# random-keypad-interface-board-v01.net
KiCad netlist of a schematic drawn in EAGLE
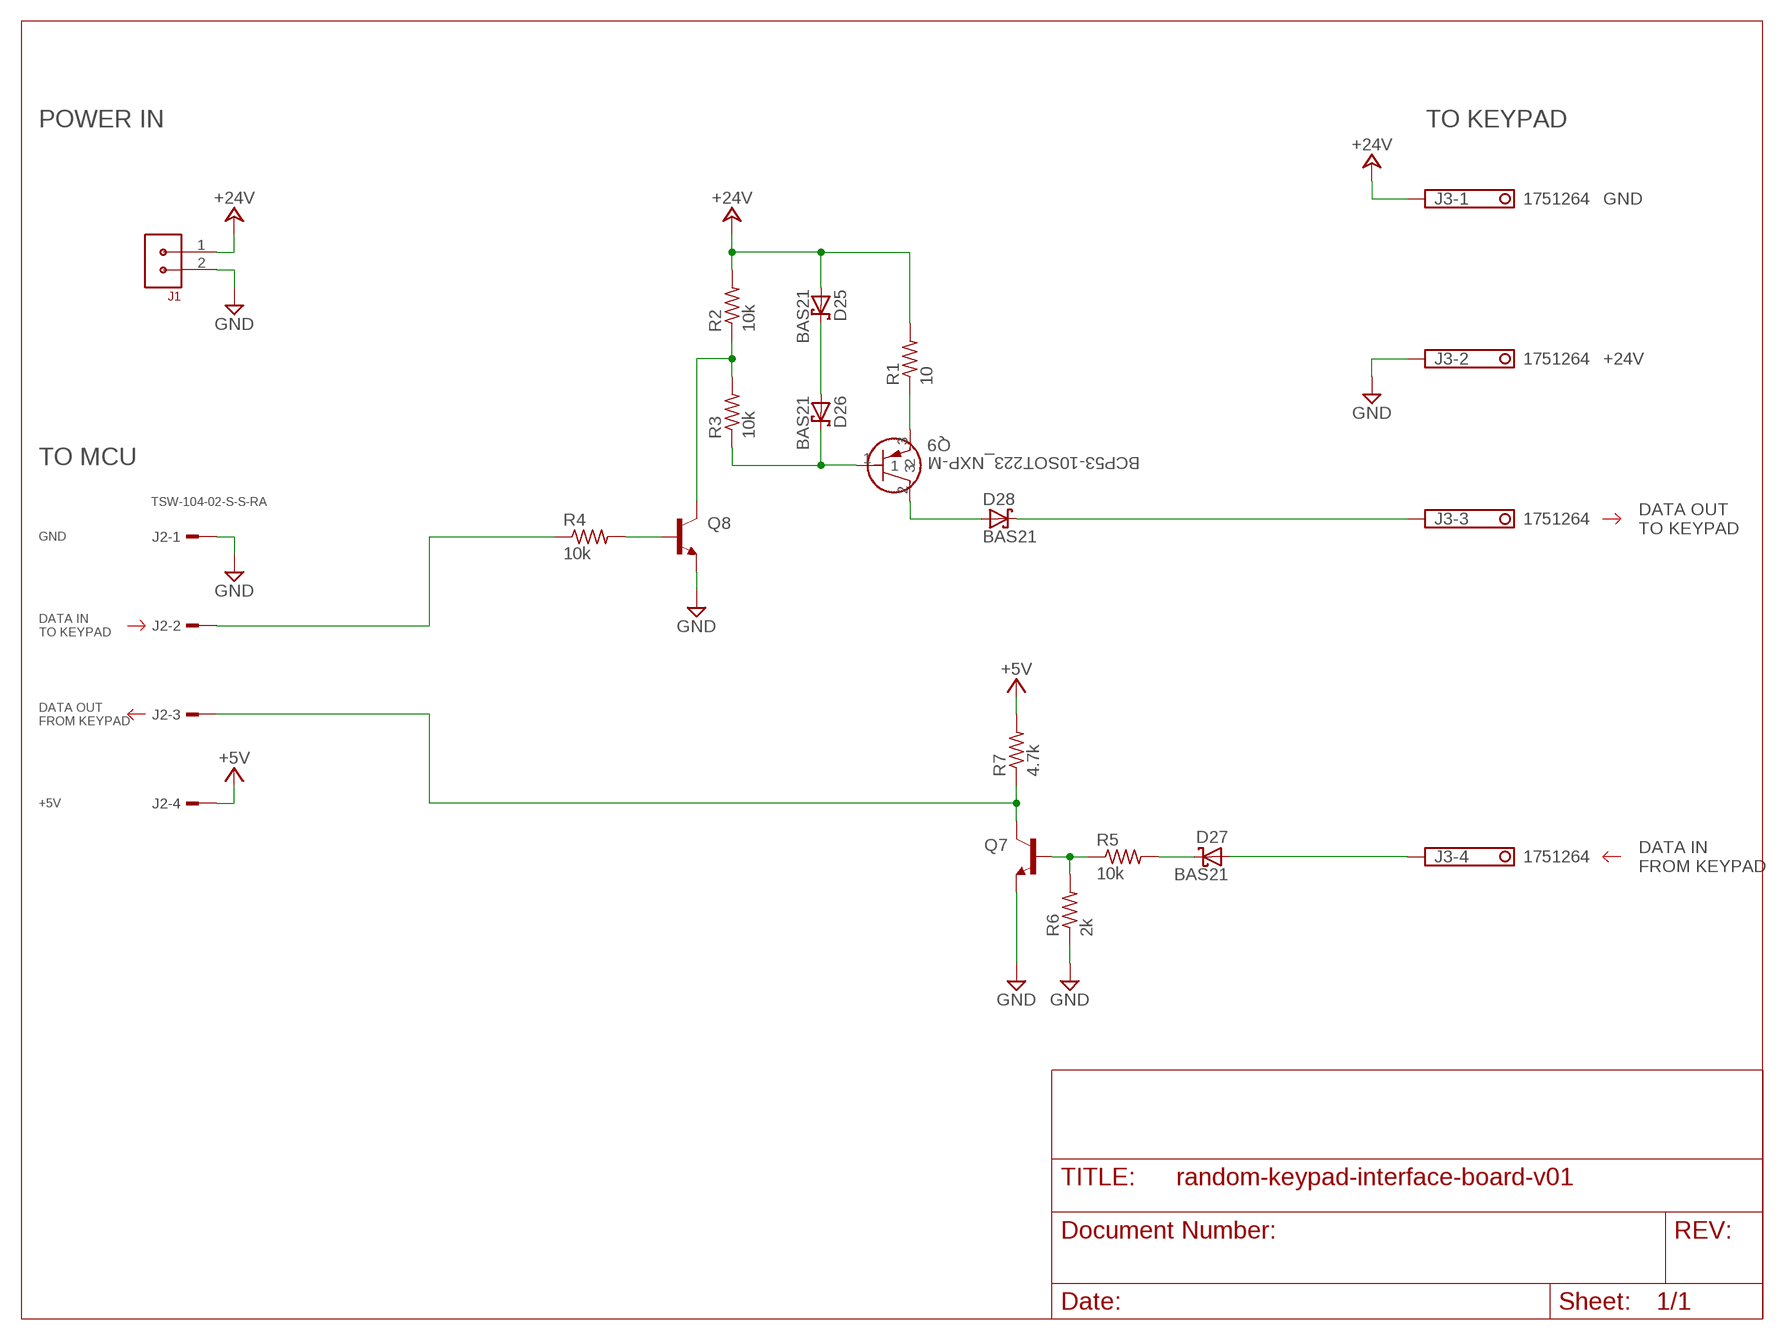
[diagram p0: schematic, sheet 1]

(export (version "E")
  (design (tool "Eeschema 10.0.6"))
  (components
    (comp (ref "D25")
      (value "BAS21")
      (footprint "eagle-import:SOT23")
      (libsource (lib "eagle-import") (part "BAS40"))
    )
    (comp (ref "D26")
      (value "BAS21")
      (footprint "eagle-import:SOT23")
      (libsource (lib "eagle-import") (part "BAS40"))
    )
    (comp (ref "D27")
      (value "BAS21")
      (footprint "eagle-import:SOT23")
      (libsource (lib "eagle-import") (part "BAS40"))
    )
    (comp (ref "D28")
      (value "BAS21")
      (footprint "eagle-import:SOT23")
      (libsource (lib "eagle-import") (part "BAS40"))
    )
    (comp (ref "J1")
      (value "CON-3.81MM-1X2-PHOENIX")
      (footprint "eagle-import:CON-PHOENIX-3.81-1X2-RA")
      (libsource (lib "eagle-import") (part "CON-3.81MM-1X2-PHOENIX"))
    )
    (comp (ref "J2")
      (value "TSW-104-02-S-S-RA")
      (footprint "eagle-import:TSW-104-02-S-S-RA")
      (libsource (lib "eagle-import") (part "TSW-104-02-S-S-RA"))
    )
    (comp (ref "J3")
      (value "1751264")
      (footprint "eagle-import:1751264")
      (libsource (lib "eagle-import") (part "1751264"))
    )
    (comp (ref "Q7")
      (value "BC817-40-NPN-SOT23-BEC")
      (footprint "eagle-import:SOT23-BEC")
      (libsource (lib "eagle-import") (part "-NPN-SOT23-BECBC817-40"))
    )
    (comp (ref "Q8")
      (value "BC817-40-NPN-SOT23-BEC")
      (footprint "eagle-import:SOT23-BEC")
      (libsource (lib "eagle-import") (part "-NPN-SOT23-BECBC817-40"))
    )
    (comp (ref "Q9")
      (value "BCP53-10SOT223_NXP-M")
      (footprint "eagle-import:SOT223_NXP-M")
      (fields
        (field (name "MANUFACTURER_PART_NUMBER") "BCP53-10")
        (field (name "COPYRIGHT") "Copyright (C) 2021 Ultra Librarian. All rights reserved.")
      )
      (libsource (lib "eagle-import") (part "BCP53-10SOT223_NXP-M"))
    )
    (comp (ref "R1")
      (value "10")
      (footprint "eagle-import:R0603")
      (libsource (lib "eagle-import") (part "R-US_R0603"))
    )
    (comp (ref "R2")
      (value "10k")
      (footprint "eagle-import:R0603")
      (libsource (lib "eagle-import") (part "R-US_R0603"))
    )
    (comp (ref "R3")
      (value "10k")
      (footprint "eagle-import:R0603")
      (libsource (lib "eagle-import") (part "R-US_R0603"))
    )
    (comp (ref "R4")
      (value "10k")
      (footprint "eagle-import:R0603")
      (libsource (lib "eagle-import") (part "R-US_R0603"))
    )
    (comp (ref "R5")
      (value "10k")
      (footprint "eagle-import:R0603")
      (libsource (lib "eagle-import") (part "R-US_R0603"))
    )
    (comp (ref "R6")
      (value "2k")
      (footprint "eagle-import:R0603")
      (libsource (lib "eagle-import") (part "R-US_R0603"))
    )
    (comp (ref "R7")
      (value "4.7k")
      (footprint "eagle-import:R0603")
      (libsource (lib "eagle-import") (part "R-US_R0603"))
    )
  )
  (nets
    (net (code "1") (name "+5V") (class "Default")
      (node (ref "J2") (pin "4") (pinfunction "1_4") (pintype "passive"))
      (node (ref "R7") (pin "2") (pinfunction "2_2") (pintype "passive"))
    )
    (net (code "2") (name "+24V") (class "Default")
      (node (ref "D25") (pin "1") (pinfunction "A_1") (pintype "passive"))
      (node (ref "J1") (pin "1") (pinfunction "1_1") (pintype "bidirectional"))
      (node (ref "J3") (pin "1") (pinfunction "K_1") (pintype "passive"))
      (node (ref "R1") (pin "2") (pinfunction "2_2") (pintype "passive"))
      (node (ref "R2") (pin "2") (pinfunction "2_2") (pintype "passive"))
    )
    (net (code "3") (name "GND") (class "Default")
      (node (ref "J1") (pin "2") (pinfunction "2_2") (pintype "bidirectional"))
      (node (ref "J2") (pin "1") (pinfunction "1_1") (pintype "passive"))
      (node (ref "J3") (pin "2") (pinfunction "K_2") (pintype "passive"))
      (node (ref "Q7") (pin "E") (pinfunction "E_E") (pintype "passive"))
      (node (ref "Q8") (pin "E") (pinfunction "E_E") (pintype "passive"))
      (node (ref "R6") (pin "1") (pinfunction "1_1") (pintype "passive"))
    )
    (net (code "4") (name "Net-(D25-C)") (class "Default")
      (node (ref "D25") (pin "3") (pinfunction "C_3") (pintype "passive"))
      (node (ref "D26") (pin "1") (pinfunction "A_1") (pintype "passive"))
    )
    (net (code "5") (name "Net-(D26-C)") (class "Default")
      (node (ref "D26") (pin "3") (pinfunction "C_3") (pintype "passive"))
      (node (ref "Q9") (pin "1") (pinfunction "1_1") (pintype "passive"))
      (node (ref "R3") (pin "1") (pinfunction "1_1") (pintype "passive"))
    )
    (net (code "6") (name "Net-(D27-A)") (class "Default")
      (node (ref "D27") (pin "1") (pinfunction "A_1") (pintype "passive"))
      (node (ref "J3") (pin "4") (pinfunction "K_4") (pintype "passive"))
    )
    (net (code "7") (name "Net-(D27-C)") (class "Default")
      (node (ref "D27") (pin "3") (pinfunction "C_3") (pintype "passive"))
      (node (ref "R5") (pin "2") (pinfunction "2_2") (pintype "passive"))
    )
    (net (code "8") (name "Net-(D28-A)") (class "Default")
      (node (ref "D28") (pin "1") (pinfunction "A_1") (pintype "passive"))
      (node (ref "Q9") (pin "2") (pinfunction "2_2") (pintype "passive"))
    )
    (net (code "9") (name "Net-(D28-C)") (class "Default")
      (node (ref "D28") (pin "3") (pinfunction "C_3") (pintype "passive"))
      (node (ref "J3") (pin "3") (pinfunction "K_3") (pintype "passive"))
    )
    (net (code "10") (name "Net-(J2B-1)") (class "Default")
      (node (ref "J2") (pin "2") (pinfunction "1_2") (pintype "passive"))
      (node (ref "R4") (pin "1") (pinfunction "1_1") (pintype "passive"))
    )
    (net (code "11") (name "Net-(J2C-1)") (class "Default")
      (node (ref "J2") (pin "3") (pinfunction "1_3") (pintype "passive"))
      (node (ref "Q7") (pin "C") (pinfunction "C_C") (pintype "passive"))
      (node (ref "R7") (pin "1") (pinfunction "1_1") (pintype "passive"))
    )
    (net (code "12") (name "Net-(Q7-PadB)") (class "Default")
      (node (ref "Q7") (pin "B") (pinfunction "B_B") (pintype "passive"))
      (node (ref "R5") (pin "1") (pinfunction "1_1") (pintype "passive"))
      (node (ref "R6") (pin "2") (pinfunction "2_2") (pintype "passive"))
    )
    (net (code "13") (name "Net-(Q8-PadB)") (class "Default")
      (node (ref "Q8") (pin "B") (pinfunction "B_B") (pintype "passive"))
      (node (ref "R4") (pin "2") (pinfunction "2_2") (pintype "passive"))
    )
    (net (code "14") (name "Net-(Q8-PadC)") (class "Default")
      (node (ref "Q8") (pin "C") (pinfunction "C_C") (pintype "passive"))
      (node (ref "R2") (pin "1") (pinfunction "1_1") (pintype "passive"))
      (node (ref "R3") (pin "2") (pinfunction "2_2") (pintype "passive"))
    )
    (net (code "15") (name "Net-(Q9-Pad3)") (class "Default")
      (node (ref "Q9") (pin "3") (pinfunction "3_3") (pintype "passive"))
      (node (ref "R1") (pin "1") (pinfunction "1_1") (pintype "passive"))
    )
  )
)
